# Sheet1.net
KiCad netlist of a schematic drawn in Altium Designer
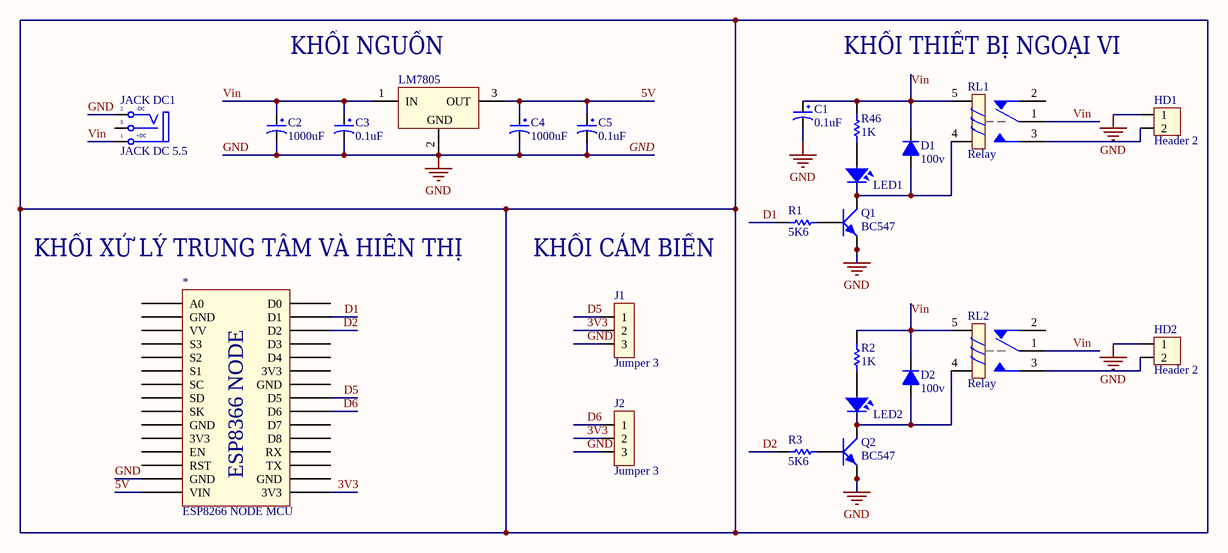
[diagram p0: Sheet1.SchDoc]

(export (version "E")
  (design (tool "Eeschema 10.0.6"))
  (components
    (comp (ref "*")
      (value "ESP8266 NODE MCU")
      (footprint "ESP8266 NODE MCU")
      (libsource (lib "Altium_Lib_by_KhueNguyenCreator") (part "ESP8266 NODE MCU"))
    )
    (comp (ref "C1")
      (value "0.1uF")
      (footprint "tu hoa 5mm")
      (description "Cắm")
      (libsource (lib "Altium_Lib_by_KhueNguyenCreator") (part "Tu Hoa 0.1uF 50V 5x11"))
    )
    (comp (ref "C2")
      (value "1000uF")
      (footprint "tu hoa 8mm")
      (description "Cắm")
      (libsource (lib "Altium_Lib_by_KhueNguyenCreator") (part "Tu Hoa 1000uF 16V 8x20"))
    )
    (comp (ref "C3")
      (value "0.1uF")
      (footprint "tu hoa 5mm")
      (description "Cắm")
      (libsource (lib "Altium_Lib_by_KhueNguyenCreator") (part "Tu Hoa 0.1uF 50V 5x11"))
    )
    (comp (ref "C4")
      (value "1000uF")
      (footprint "tu hoa 8mm")
      (description "Cắm")
      (libsource (lib "Altium_Lib_by_KhueNguyenCreator") (part "Tu Hoa 1000uF 16V 8x20"))
    )
    (comp (ref "C5")
      (value "0.1uF")
      (footprint "tu hoa 5mm")
      (description "Cắm")
      (libsource (lib "Altium_Lib_by_KhueNguyenCreator") (part "Tu Hoa 0.1uF 50V 5x11"))
    )
    (comp (ref "D1")
      (value "100v")
      (footprint "DIODE 1A")
      (description "Cắm")
      (libsource (lib "Altium_Lib_by_KhueNguyenCreator") (part "Diode 1N4007"))
    )
    (comp (ref "D2")
      (value "100v")
      (footprint "DIODE 1A")
      (description "Cắm")
      (libsource (lib "Altium_Lib_by_KhueNguyenCreator") (part "Diode 1N4007"))
    )
    (comp (ref "HD1")
      (value "Header 2")
      (footprint "HED2")
      (description "Header 2 (Green)")
      (libsource (lib "syhaunguyen") (part "Hed2"))
    )
    (comp (ref "HD2")
      (value "Header 2")
      (footprint "HED2")
      (description "Header 2 (Green)")
      (libsource (lib "syhaunguyen") (part "Hed2"))
    )
    (comp (ref "IC1")
      (value "LM7805")
      (footprint "QTO-220H1")
      (libsource (lib "My library altium") (part "LD78M05"))
    )
    (comp (ref "J1") (value "Jumper 3") (footprint "JP3") (libsource (lib "syhaunguyen") (part "JP3")))
    (comp (ref "J2") (value "Jumper 3") (footprint "JP3") (libsource (lib "syhaunguyen") (part "JP3")))
    (comp (ref "JACK DC1")
      (value "JACK DC 5.5")
      (footprint "JACK DC 5.5")
      (libsource (lib "Altium_Lib_by_KhueNguyenCreator") (part "JACK DC 5.5"))
    )
    (comp (ref "LED1")
      (value "LED")
      (footprint "LED-3")
      (description "LED Single colour Green and Red")
      (libsource (lib "syhaunguyen") (part "LED"))
    )
    (comp (ref "LED2")
      (value "LED")
      (footprint "LED-3")
      (description "LED Single colour Green and Red")
      (libsource (lib "syhaunguyen") (part "LED"))
    )
    (comp (ref "Q1") (value "BC547") (footprint "TO92") (libsource (lib "BC547") (part "BC547")))
    (comp (ref "Q2") (value "BC547") (footprint "TO92") (libsource (lib "BC547") (part "BC547")))
    (comp (ref "R1")
      (value "5K6")
      (footprint "R1/4W")
      (description "Resistor")
      (fields
        (field (name "MANUFACTURER") "Generic Components")
        (field (name "Comment") "Res1")
        (field (name "PUBLISHER") "Altium Hobart Technology Centre")
      )
      (libsource (lib "syhaunguyen") (part "Res1_1"))
    )
    (comp (ref "R2")
      (value "1K")
      (footprint "R1/4W")
      (description "Resistor")
      (fields
        (field (name "MANUFACTURER") "Generic Components")
        (field (name "Comment") "Res1")
        (field (name "PUBLISHER") "Altium Hobart Technology Centre")
      )
      (libsource (lib "syhaunguyen") (part "Res1_1"))
    )
    (comp (ref "R3")
      (value "5K6")
      (footprint "R1/4W")
      (description "Resistor")
      (fields
        (field (name "MANUFACTURER") "Generic Components")
        (field (name "Comment") "Res1")
        (field (name "PUBLISHER") "Altium Hobart Technology Centre")
      )
      (libsource (lib "syhaunguyen") (part "Res1_1"))
    )
    (comp (ref "R46")
      (value "1K")
      (footprint "R1/4W")
      (description "Resistor")
      (fields
        (field (name "MANUFACTURER") "Generic Components")
        (field (name "Comment") "Res1")
        (field (name "PUBLISHER") "Altium Hobart Technology Centre")
      )
      (libsource (lib "syhaunguyen") (part "Res1_1"))
    )
    (comp (ref "RL1")
      (value "Relay")
      (footprint "Relay 5 Chan SRD")
      (description "Relay 5 Chan")
      (libsource (lib "Altium_Lib_by_KhueNguyenCreator") (part "Relay 5 Chan SRD"))
    )
    (comp (ref "RL2")
      (value "Relay")
      (footprint "Relay 5 Chan SRD")
      (description "Relay 5 Chan")
      (libsource (lib "Altium_Lib_by_KhueNguyenCreator") (part "Relay 5 Chan SRD"))
    )
  )
  (nets
    (net (code "1") (name "/3V3") (class "Default")
      (node (ref "*") (pin "16") (pinfunction "3V3_16") (pintype "passive"))
      (node (ref "J1") (pin "2") (pinfunction "2_2") (pintype "passive"))
      (node (ref "J2") (pin "2") (pinfunction "2_2") (pintype "passive"))
    )
    (net (code "2") (name "/5V") (class "Default")
      (node (ref "*") (pin "15") (pinfunction "VIN_15") (pintype "passive"))
      (node (ref "C4") (pin "1") (pinfunction "1_1") (pintype "passive"))
      (node (ref "C5") (pin "1") (pinfunction "1_1") (pintype "passive"))
      (node (ref "IC1") (pin "3") (pinfunction "OUT_3") (pintype "passive"))
    )
    (net (code "3") (name "/D1") (class "Default")
      (node (ref "*") (pin "29") (pinfunction "D1_29") (pintype "passive"))
      (node (ref "R1") (pin "2") (pinfunction "2_2") (pintype "passive"))
    )
    (net (code "4") (name "/D2") (class "Default")
      (node (ref "*") (pin "28") (pinfunction "D2_28") (pintype "passive"))
      (node (ref "R3") (pin "2") (pinfunction "2_2") (pintype "passive"))
    )
    (net (code "5") (name "/D5") (class "Default")
      (node (ref "*") (pin "23") (pinfunction "D5_23") (pintype "passive"))
      (node (ref "J1") (pin "1") (pinfunction "1_1") (pintype "passive"))
    )
    (net (code "6") (name "/D6") (class "Default")
      (node (ref "*") (pin "22") (pinfunction "D6_22") (pintype "passive"))
      (node (ref "J2") (pin "1") (pinfunction "1_1") (pintype "passive"))
    )
    (net (code "7") (name "/Vin") (class "Default")
      (node (ref "C1") (pin "1") (pinfunction "1_1") (pintype "passive"))
      (node (ref "C2") (pin "1") (pinfunction "1_1") (pintype "passive"))
      (node (ref "C3") (pin "1") (pinfunction "1_1") (pintype "passive"))
      (node (ref "D1") (pin "2") (pinfunction "K_2") (pintype "passive"))
      (node (ref "D2") (pin "2") (pinfunction "K_2") (pintype "passive"))
      (node (ref "IC1") (pin "1") (pinfunction "IN_1") (pintype "passive"))
      (node (ref "JACK DC1") (pin "1") (pinfunction "T_1") (pintype "passive"))
      (node (ref "R2") (pin "2") (pinfunction "2_2") (pintype "passive"))
      (node (ref "R46") (pin "2") (pinfunction "2_2") (pintype "passive"))
      (node (ref "RL1") (pin "1") (pinfunction "1_1") (pintype "passive"))
      (node (ref "RL1") (pin "5") (pinfunction "5_5") (pintype "passive"))
      (node (ref "RL2") (pin "1") (pinfunction "1_1") (pintype "passive"))
      (node (ref "RL2") (pin "5") (pinfunction "5_5") (pintype "passive"))
    )
    (net (code "8") (name "GND") (class "Default")
      (node (ref "*") (pin "14") (pinfunction "GND_14") (pintype "passive"))
      (node (ref "C1") (pin "2") (pinfunction "2_2") (pintype "passive"))
      (node (ref "C2") (pin "2") (pinfunction "2_2") (pintype "passive"))
      (node (ref "C3") (pin "2") (pinfunction "2_2") (pintype "passive"))
      (node (ref "C4") (pin "2") (pinfunction "2_2") (pintype "passive"))
      (node (ref "C5") (pin "2") (pinfunction "2_2") (pintype "passive"))
      (node (ref "HD1") (pin "1") (pinfunction "1_1") (pintype "passive"))
      (node (ref "HD2") (pin "1") (pinfunction "1_1") (pintype "passive"))
      (node (ref "IC1") (pin "2") (pinfunction "GND_2") (pintype "passive"))
      (node (ref "J1") (pin "3") (pinfunction "3_3") (pintype "passive"))
      (node (ref "J2") (pin "3") (pinfunction "3_3") (pintype "passive"))
      (node (ref "JACK DC1") (pin "2") (pinfunction "TN_2") (pintype "passive"))
      (node (ref "Q1") (pin "3") (pinfunction "E_3") (pintype "passive"))
      (node (ref "Q2") (pin "3") (pinfunction "E_3") (pintype "passive"))
    )
    (net (code "9") (name "Net-(D1-A)") (class "Default")
      (node (ref "D1") (pin "1") (pinfunction "A_1") (pintype "passive"))
      (node (ref "LED1") (pin "2") (pinfunction "2_2") (pintype "passive"))
      (node (ref "Q1") (pin "1") (pinfunction "C_1") (pintype "passive"))
      (node (ref "RL1") (pin "4") (pinfunction "4_4") (pintype "passive"))
    )
    (net (code "10") (name "Net-(D2-A)") (class "Default")
      (node (ref "D2") (pin "1") (pinfunction "A_1") (pintype "passive"))
      (node (ref "LED2") (pin "2") (pinfunction "2_2") (pintype "passive"))
      (node (ref "Q2") (pin "1") (pinfunction "C_1") (pintype "passive"))
      (node (ref "RL2") (pin "4") (pinfunction "4_4") (pintype "passive"))
    )
    (net (code "11") (name "Net-(HD1-Pad2)") (class "Default")
      (node (ref "HD1") (pin "2") (pinfunction "2_2") (pintype "passive"))
      (node (ref "RL1") (pin "3") (pinfunction "3_3") (pintype "passive"))
    )
    (net (code "12") (name "Net-(HD2-Pad2)") (class "Default")
      (node (ref "HD2") (pin "2") (pinfunction "2_2") (pintype "passive"))
      (node (ref "RL2") (pin "3") (pinfunction "3_3") (pintype "passive"))
    )
    (net (code "13") (name "Net-(LED1-Pad1)") (class "Default")
      (node (ref "LED1") (pin "1") (pinfunction "1_1") (pintype "passive"))
      (node (ref "R46") (pin "1") (pinfunction "1_1") (pintype "passive"))
    )
    (net (code "14") (name "Net-(LED2-Pad1)") (class "Default")
      (node (ref "LED2") (pin "1") (pinfunction "1_1") (pintype "passive"))
      (node (ref "R2") (pin "1") (pinfunction "1_1") (pintype "passive"))
    )
    (net (code "15") (name "Net-(Q1-B)") (class "Default")
      (node (ref "Q1") (pin "2") (pinfunction "B_2") (pintype "passive"))
      (node (ref "R1") (pin "1") (pinfunction "1_1") (pintype "passive"))
    )
    (net (code "16") (name "Net-(Q2-B)") (class "Default")
      (node (ref "Q2") (pin "2") (pinfunction "B_2") (pintype "passive"))
      (node (ref "R3") (pin "1") (pinfunction "1_1") (pintype "passive"))
    )
    (net (code "17") (name "unconnected-(*-3V3-Pad11)") (class "Default")
      (node (ref "*") (pin "11") (pinfunction "3V3_11") (pintype "passive"))
    )
    (net (code "18") (name "unconnected-(*-3V3-Pad25)") (class "Default")
      (node (ref "*") (pin "25") (pinfunction "3V3_25") (pintype "passive"))
    )
    (net (code "19") (name "unconnected-(*-A0-Pad1)") (class "Default")
      (node (ref "*") (pin "1") (pinfunction "A0_1") (pintype "passive"))
    )
    (net (code "20") (name "unconnected-(*-D0-Pad30)") (class "Default")
      (node (ref "*") (pin "30") (pinfunction "D0_30") (pintype "passive"))
    )
    (net (code "21") (name "unconnected-(*-D3-Pad27)") (class "Default")
      (node (ref "*") (pin "27") (pinfunction "D3_27") (pintype "passive"))
    )
    (net (code "22") (name "unconnected-(*-D4-Pad26)") (class "Default")
      (node (ref "*") (pin "26") (pinfunction "D4_26") (pintype "passive"))
    )
    (net (code "23") (name "unconnected-(*-D7-Pad21)") (class "Default")
      (node (ref "*") (pin "21") (pinfunction "D7_21") (pintype "passive"))
    )
    (net (code "24") (name "unconnected-(*-D8-Pad20)") (class "Default")
      (node (ref "*") (pin "20") (pinfunction "D8_20") (pintype "passive"))
    )
    (net (code "25") (name "unconnected-(*-EN-Pad12)") (class "Default")
      (node (ref "*") (pin "12") (pinfunction "EN_12") (pintype "passive"))
    )
    (net (code "26") (name "unconnected-(*-GND-Pad2)") (class "Default")
      (node (ref "*") (pin "2") (pinfunction "GND_2") (pintype "passive"))
    )
    (net (code "27") (name "unconnected-(*-GND-Pad10)") (class "Default")
      (node (ref "*") (pin "10") (pinfunction "GND_10") (pintype "passive"))
    )
    (net (code "28") (name "unconnected-(*-GND-Pad17)") (class "Default")
      (node (ref "*") (pin "17") (pinfunction "GND_17") (pintype "passive"))
    )
    (net (code "29") (name "unconnected-(*-GND-Pad24)") (class "Default")
      (node (ref "*") (pin "24") (pinfunction "GND_24") (pintype "passive"))
    )
    (net (code "30") (name "unconnected-(*-RST-Pad13)") (class "Default")
      (node (ref "*") (pin "13") (pinfunction "RST_13") (pintype "passive"))
    )
    (net (code "31") (name "unconnected-(*-RX-Pad19)") (class "Default")
      (node (ref "*") (pin "19") (pinfunction "RX_19") (pintype "passive"))
    )
    (net (code "32") (name "unconnected-(*-S1-Pad6)") (class "Default")
      (node (ref "*") (pin "6") (pinfunction "S1_6") (pintype "passive"))
    )
    (net (code "33") (name "unconnected-(*-S2-Pad5)") (class "Default")
      (node (ref "*") (pin "5") (pinfunction "S2_5") (pintype "passive"))
    )
    (net (code "34") (name "unconnected-(*-S3-Pad4)") (class "Default")
      (node (ref "*") (pin "4") (pinfunction "S3_4") (pintype "passive"))
    )
    (net (code "35") (name "unconnected-(*-SC-Pad7)") (class "Default")
      (node (ref "*") (pin "7") (pinfunction "SC_7") (pintype "passive"))
    )
    (net (code "36") (name "unconnected-(*-SD-Pad8)") (class "Default")
      (node (ref "*") (pin "8") (pinfunction "SD_8") (pintype "passive"))
    )
    (net (code "37") (name "unconnected-(*-SK-Pad9)") (class "Default")
      (node (ref "*") (pin "9") (pinfunction "SK_9") (pintype "passive"))
    )
    (net (code "38") (name "unconnected-(*-TX-Pad18)") (class "Default")
      (node (ref "*") (pin "18") (pinfunction "TX_18") (pintype "passive"))
    )
    (net (code "39") (name "unconnected-(*-VV-Pad3)") (class "Default")
      (node (ref "*") (pin "3") (pinfunction "VV_3") (pintype "passive"))
    )
    (net (code "40") (name "unconnected-(JACK DC1-S-Pad3)") (class "Default")
      (node (ref "JACK DC1") (pin "3") (pinfunction "S_3") (pintype "power_in"))
    )
    (net (code "41") (name "unconnected-(RL1-Pad2)") (class "Default")
      (node (ref "RL1") (pin "2") (pinfunction "2_2") (pintype "passive"))
    )
    (net (code "42") (name "unconnected-(RL2-Pad2)") (class "Default")
      (node (ref "RL2") (pin "2") (pinfunction "2_2") (pintype "passive"))
    )
  )
)
